# sensors.net
KiCad netlist of a schematic drawn in Altium Designer
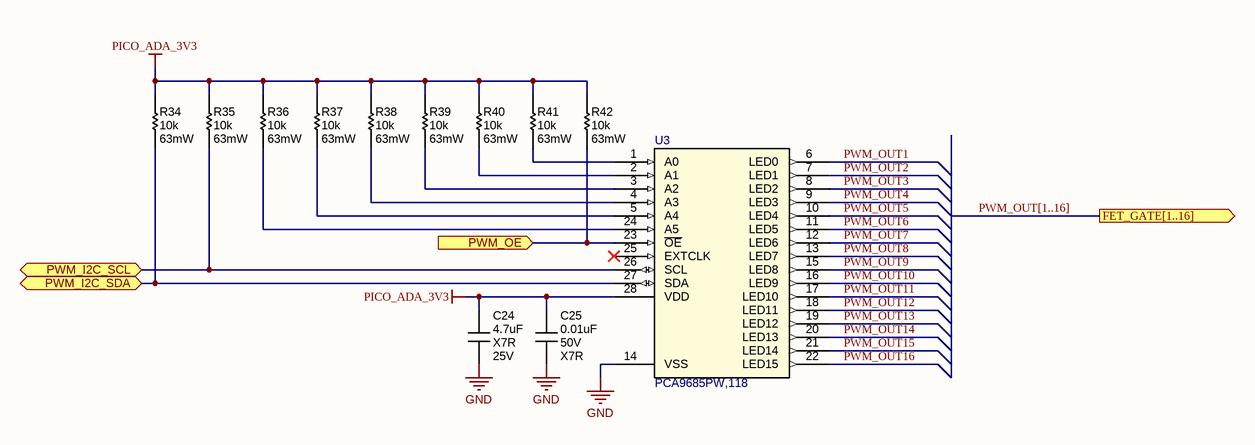
[diagram p0: sensors.SchDoc]

(export (version "E")
  (design (tool "Eeschema 10.0.6"))
  (components
    (comp (ref "C24")
      (value "4.7uF")
      (footprint "CAPC2012X14N")
      (description "CAP CER 4.7UF 25V X7R 0805")
      (fields
        (field (name "MFR") "TDK Corporation")
        (field (name "TOLERANCE") "10%")
        (field (name "TEMP COEFF") "X7R")
        (field (name "VOLTAGE RATING") "25V")
      )
      (libsource (lib "General_Library") (part "CMP-004-0011"))
    )
    (comp (ref "C25")
      (value "0.01uF")
      (footprint "CAPC1005X06N")
      (description "CAP CER SMD 0.01UF 50V X7R 0402")
      (fields
        (field (name "TOLERANCE") "10%")
        (field (name "MFR") "Murata Electronics")
        (field (name "VOLTAGE RATING") "50V")
        (field (name "TEMP COEFF") "X7R")
      )
      (libsource (lib "General_Library") (part "CMP-004-0077"))
    )
    (comp (ref "R34")
      (value "10k")
      (footprint "RESC1005X04N")
      (description "RES SMD 10K OHM 0.5% 1/16W 0402")
      (fields
        (field (name "MFR") "Panasonic Electronic Components")
        (field (name "TOLERANCE") "0.5%")
        (field (name "WATTAGE") "63mW")
      )
      (libsource (lib "General_Library") (part "CMP-025-0026"))
    )
    (comp (ref "R35")
      (value "10k")
      (footprint "RESC1005X04N")
      (description "RES SMD 10K OHM 0.5% 1/16W 0402")
      (fields
        (field (name "MFR") "Panasonic Electronic Components")
        (field (name "TOLERANCE") "0.5%")
        (field (name "WATTAGE") "63mW")
      )
      (libsource (lib "General_Library") (part "CMP-025-0026"))
    )
    (comp (ref "R36")
      (value "10k")
      (footprint "RESC1005X04N")
      (description "RES SMD 10K OHM 0.5% 1/16W 0402")
      (fields
        (field (name "MFR") "Panasonic Electronic Components")
        (field (name "TOLERANCE") "0.5%")
        (field (name "WATTAGE") "63mW")
      )
      (libsource (lib "General_Library") (part "CMP-025-0026"))
    )
    (comp (ref "R37")
      (value "10k")
      (footprint "RESC1005X04N")
      (description "RES SMD 10K OHM 0.5% 1/16W 0402")
      (fields
        (field (name "MFR") "Panasonic Electronic Components")
        (field (name "TOLERANCE") "0.5%")
        (field (name "WATTAGE") "63mW")
      )
      (libsource (lib "General_Library") (part "CMP-025-0026"))
    )
    (comp (ref "R38")
      (value "10k")
      (footprint "RESC1005X04N")
      (description "RES SMD 10K OHM 0.5% 1/16W 0402")
      (fields
        (field (name "MFR") "Panasonic Electronic Components")
        (field (name "TOLERANCE") "0.5%")
        (field (name "WATTAGE") "63mW")
      )
      (libsource (lib "General_Library") (part "CMP-025-0026"))
    )
    (comp (ref "R39")
      (value "10k")
      (footprint "RESC1005X04N")
      (description "RES SMD 10K OHM 0.5% 1/16W 0402")
      (fields
        (field (name "MFR") "Panasonic Electronic Components")
        (field (name "TOLERANCE") "0.5%")
        (field (name "WATTAGE") "63mW")
      )
      (libsource (lib "General_Library") (part "CMP-025-0026"))
    )
    (comp (ref "R40")
      (value "10k")
      (footprint "RESC1005X04N")
      (description "RES SMD 10K OHM 0.5% 1/16W 0402")
      (fields
        (field (name "MFR") "Panasonic Electronic Components")
        (field (name "TOLERANCE") "0.5%")
        (field (name "WATTAGE") "63mW")
      )
      (libsource (lib "General_Library") (part "CMP-025-0026"))
    )
    (comp (ref "R41")
      (value "10k")
      (footprint "RESC1005X04N")
      (description "RES SMD 10K OHM 0.5% 1/16W 0402")
      (fields
        (field (name "MFR") "Panasonic Electronic Components")
        (field (name "TOLERANCE") "0.5%")
        (field (name "WATTAGE") "63mW")
      )
      (libsource (lib "General_Library") (part "CMP-025-0026"))
    )
    (comp (ref "R42")
      (value "10k")
      (footprint "RESC1005X04N")
      (description "RES SMD 10K OHM 0.5% 1/16W 0402")
      (fields
        (field (name "MFR") "Panasonic Electronic Components")
        (field (name "TOLERANCE") "0.5%")
        (field (name "WATTAGE") "63mW")
      )
      (libsource (lib "General_Library") (part "CMP-025-0026"))
    )
    (comp (ref "U3")
      (value "PCA9685PW,118")
      (description "IC LED DRVR LIN PWM 25MA 28TSSOP")
      (fields (field (name "MFR") "NXP"))
      (libsource (lib "General_Library") (part "CMP-017-0111"))
    )
  )
  (nets
    (net (code "1") (name "/PWM_I2C_SCL") (class "Default")
      (node (ref "R35") (pin "1") (pinfunction "1_1") (pintype "passive"))
      (node (ref "U3") (pin "26") (pinfunction "SCL_26") (pintype "bidirectional"))
    )
    (net (code "2") (name "/PWM_I2C_SDA") (class "Default")
      (node (ref "R34") (pin "1") (pinfunction "1_1") (pintype "passive"))
      (node (ref "U3") (pin "27") (pinfunction "SDA_27") (pintype "bidirectional"))
    )
    (net (code "3") (name "/PWM_OE") (class "Default")
      (node (ref "R42") (pin "1") (pinfunction "1_1") (pintype "passive"))
      (node (ref "U3") (pin "23") (pinfunction "~{OE}_23") (pintype "input"))
    )
    (net (code "4") (name "/PWM_OUT1") (class "Default")
      (node (ref "U3") (pin "6") (pinfunction "LED0_6") (pintype "output"))
    )
    (net (code "5") (name "/PWM_OUT2") (class "Default")
      (node (ref "U3") (pin "7") (pinfunction "LED1_7") (pintype "output"))
    )
    (net (code "6") (name "/PWM_OUT3") (class "Default")
      (node (ref "U3") (pin "8") (pinfunction "LED2_8") (pintype "output"))
    )
    (net (code "7") (name "/PWM_OUT4") (class "Default")
      (node (ref "U3") (pin "9") (pinfunction "LED3_9") (pintype "output"))
    )
    (net (code "8") (name "/PWM_OUT5") (class "Default")
      (node (ref "U3") (pin "10") (pinfunction "LED4_10") (pintype "output"))
    )
    (net (code "9") (name "/PWM_OUT6") (class "Default")
      (node (ref "U3") (pin "11") (pinfunction "LED5_11") (pintype "output"))
    )
    (net (code "10") (name "/PWM_OUT7") (class "Default")
      (node (ref "U3") (pin "12") (pinfunction "LED6_12") (pintype "output"))
    )
    (net (code "11") (name "/PWM_OUT8") (class "Default")
      (node (ref "U3") (pin "13") (pinfunction "LED7_13") (pintype "output"))
    )
    (net (code "12") (name "/PWM_OUT9") (class "Default")
      (node (ref "U3") (pin "15") (pinfunction "LED8_15") (pintype "output"))
    )
    (net (code "13") (name "/PWM_OUT10") (class "Default")
      (node (ref "U3") (pin "16") (pinfunction "LED9_16") (pintype "output"))
    )
    (net (code "14") (name "/PWM_OUT11") (class "Default")
      (node (ref "U3") (pin "17") (pinfunction "LED10_17") (pintype "output"))
    )
    (net (code "15") (name "/PWM_OUT12") (class "Default")
      (node (ref "U3") (pin "18") (pinfunction "LED11_18") (pintype "output"))
    )
    (net (code "16") (name "/PWM_OUT13") (class "Default")
      (node (ref "U3") (pin "19") (pinfunction "LED12_19") (pintype "output"))
    )
    (net (code "17") (name "/PWM_OUT14") (class "Default")
      (node (ref "U3") (pin "20") (pinfunction "LED13_20") (pintype "output"))
    )
    (net (code "18") (name "/PWM_OUT15") (class "Default")
      (node (ref "U3") (pin "21") (pinfunction "LED14_21") (pintype "output"))
    )
    (net (code "19") (name "/PWM_OUT16") (class "Default")
      (node (ref "U3") (pin "22") (pinfunction "LED15_22") (pintype "output"))
    )
    (net (code "21") (name "GND") (class "Default")
      (node (ref "C24") (pin "2") (pinfunction "2_2") (pintype "passive"))
      (node (ref "C25") (pin "2") (pinfunction "2_2") (pintype "passive"))
      (node (ref "U3") (pin "14") (pinfunction "VSS_14") (pintype "power_in"))
    )
    (net (code "22") (name "Net-(U3-A0)") (class "Default")
      (node (ref "R41") (pin "1") (pinfunction "1_1") (pintype "passive"))
      (node (ref "U3") (pin "1") (pinfunction "A0_1") (pintype "input"))
    )
    (net (code "23") (name "Net-(U3-A1)") (class "Default")
      (node (ref "R40") (pin "1") (pinfunction "1_1") (pintype "passive"))
      (node (ref "U3") (pin "2") (pinfunction "A1_2") (pintype "input"))
    )
    (net (code "24") (name "Net-(U3-A2)") (class "Default")
      (node (ref "R39") (pin "1") (pinfunction "1_1") (pintype "passive"))
      (node (ref "U3") (pin "3") (pinfunction "A2_3") (pintype "input"))
    )
    (net (code "25") (name "Net-(U3-A3)") (class "Default")
      (node (ref "R38") (pin "1") (pinfunction "1_1") (pintype "passive"))
      (node (ref "U3") (pin "4") (pinfunction "A3_4") (pintype "input"))
    )
    (net (code "26") (name "Net-(U3-A4)") (class "Default")
      (node (ref "R37") (pin "1") (pinfunction "1_1") (pintype "passive"))
      (node (ref "U3") (pin "5") (pinfunction "A4_5") (pintype "input"))
    )
    (net (code "27") (name "Net-(U3-A5)") (class "Default")
      (node (ref "R36") (pin "1") (pinfunction "1_1") (pintype "passive"))
      (node (ref "U3") (pin "24") (pinfunction "A5_24") (pintype "input"))
    )
    (net (code "28") (name "PICO_ADA_3V3") (class "Default")
      (node (ref "C24") (pin "1") (pinfunction "1_1") (pintype "passive"))
      (node (ref "C25") (pin "1") (pinfunction "1_1") (pintype "passive"))
      (node (ref "R34") (pin "2") (pinfunction "2_2") (pintype "passive"))
      (node (ref "R35") (pin "2") (pinfunction "2_2") (pintype "passive"))
      (node (ref "R36") (pin "2") (pinfunction "2_2") (pintype "passive"))
      (node (ref "R37") (pin "2") (pinfunction "2_2") (pintype "passive"))
      (node (ref "R38") (pin "2") (pinfunction "2_2") (pintype "passive"))
      (node (ref "R39") (pin "2") (pinfunction "2_2") (pintype "passive"))
      (node (ref "R40") (pin "2") (pinfunction "2_2") (pintype "passive"))
      (node (ref "R41") (pin "2") (pinfunction "2_2") (pintype "passive"))
      (node (ref "R42") (pin "2") (pinfunction "2_2") (pintype "passive"))
      (node (ref "U3") (pin "28") (pinfunction "VDD_28") (pintype "power_in"))
    )
    (net (code "29") (name "unconnected-(U3-EXTCLK-Pad25)") (class "Default")
      (node (ref "U3") (pin "25") (pinfunction "EXTCLK_25") (pintype "input+no_connect"))
    )
  )
)
